# mattduino_mega_nano_v7.net
KiCad netlist of a schematic drawn in EAGLE
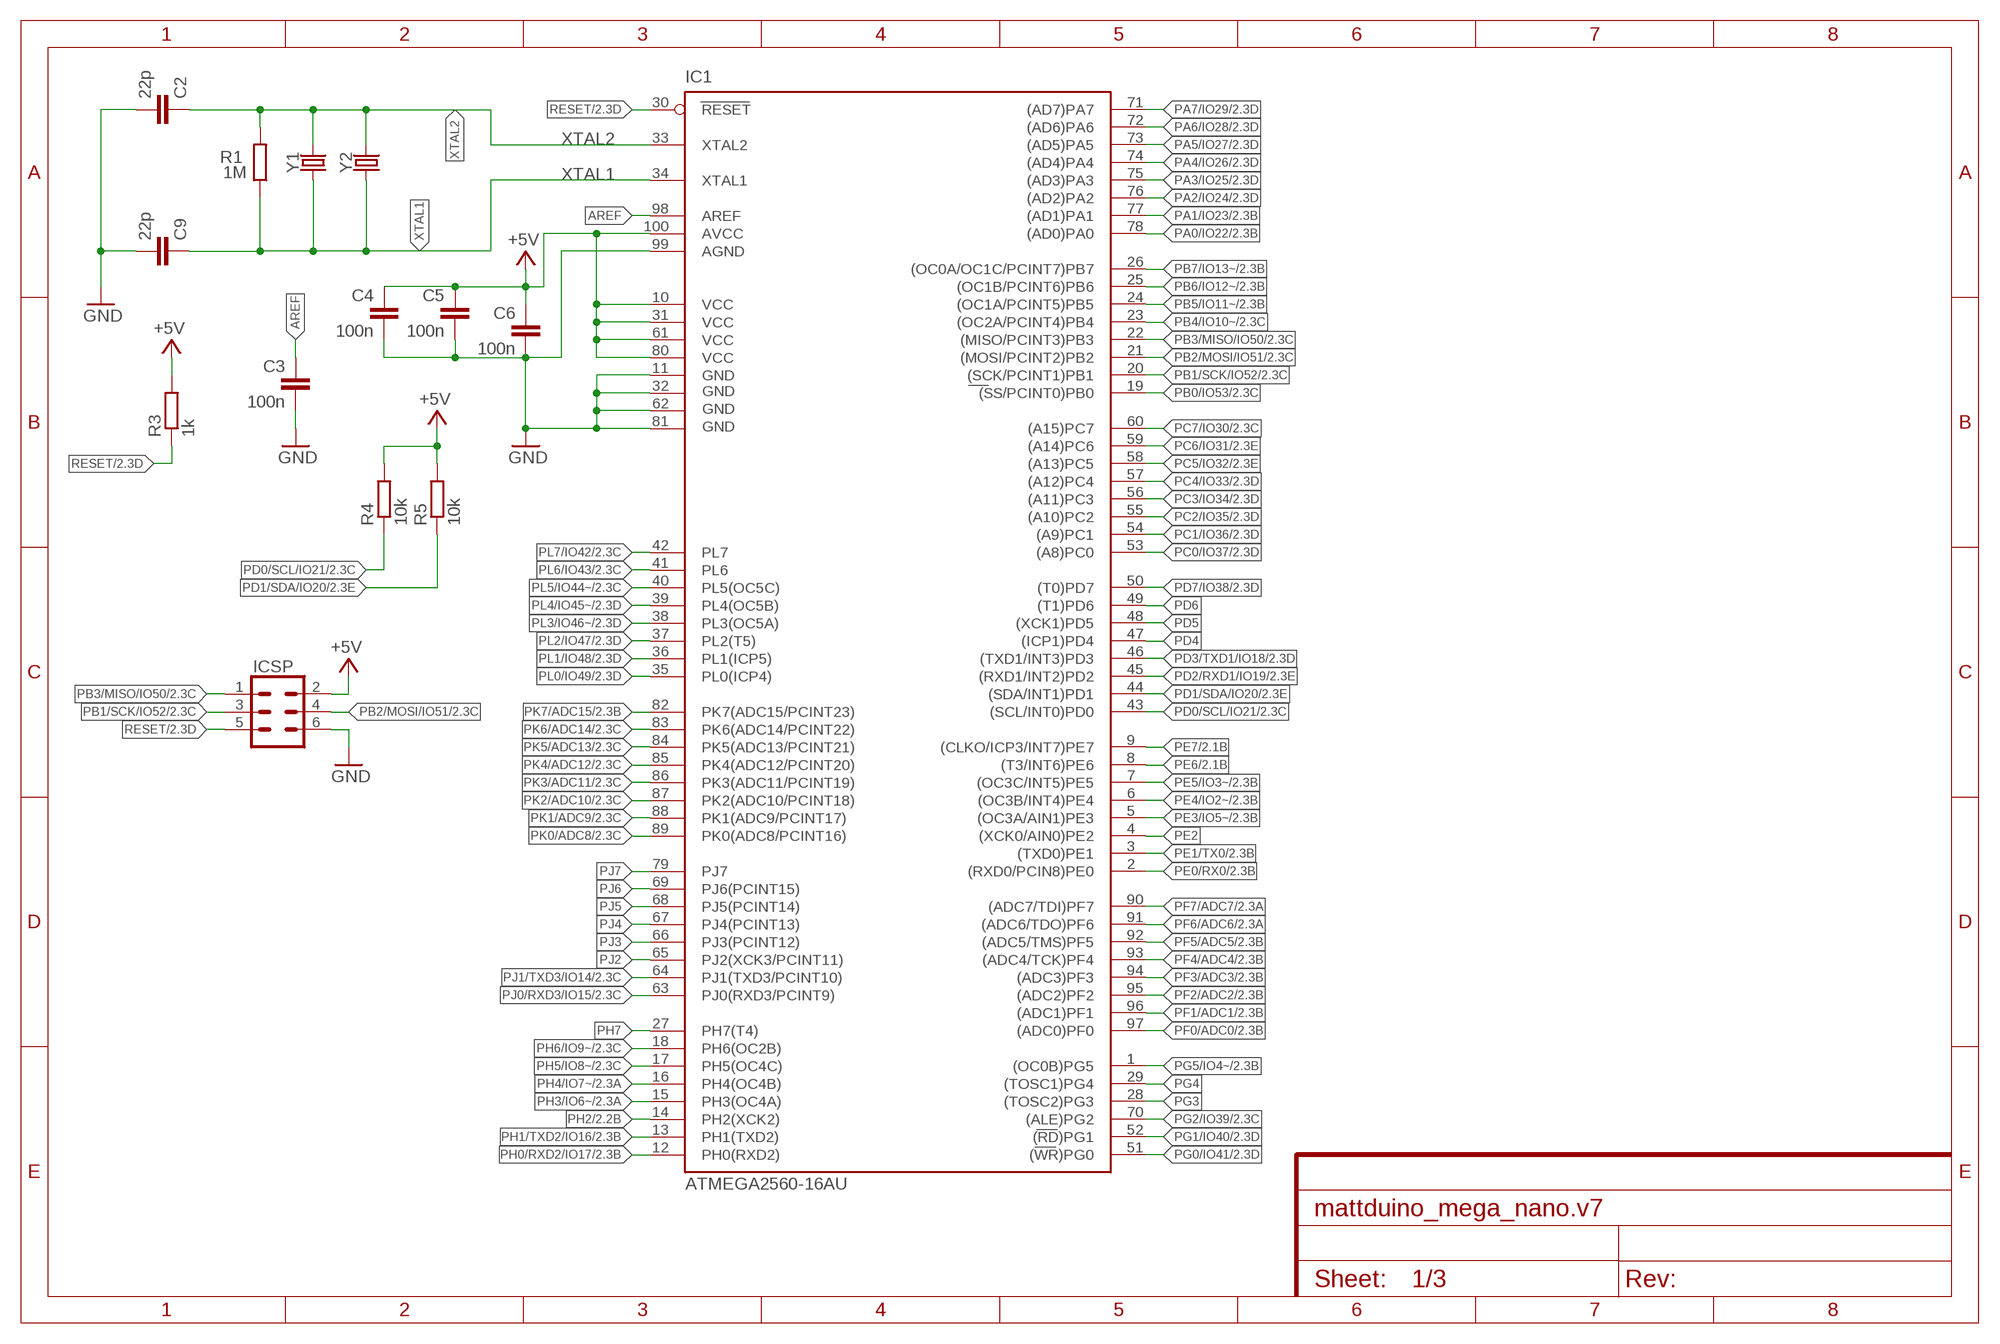
[diagram p0: schematic, sheet 1]
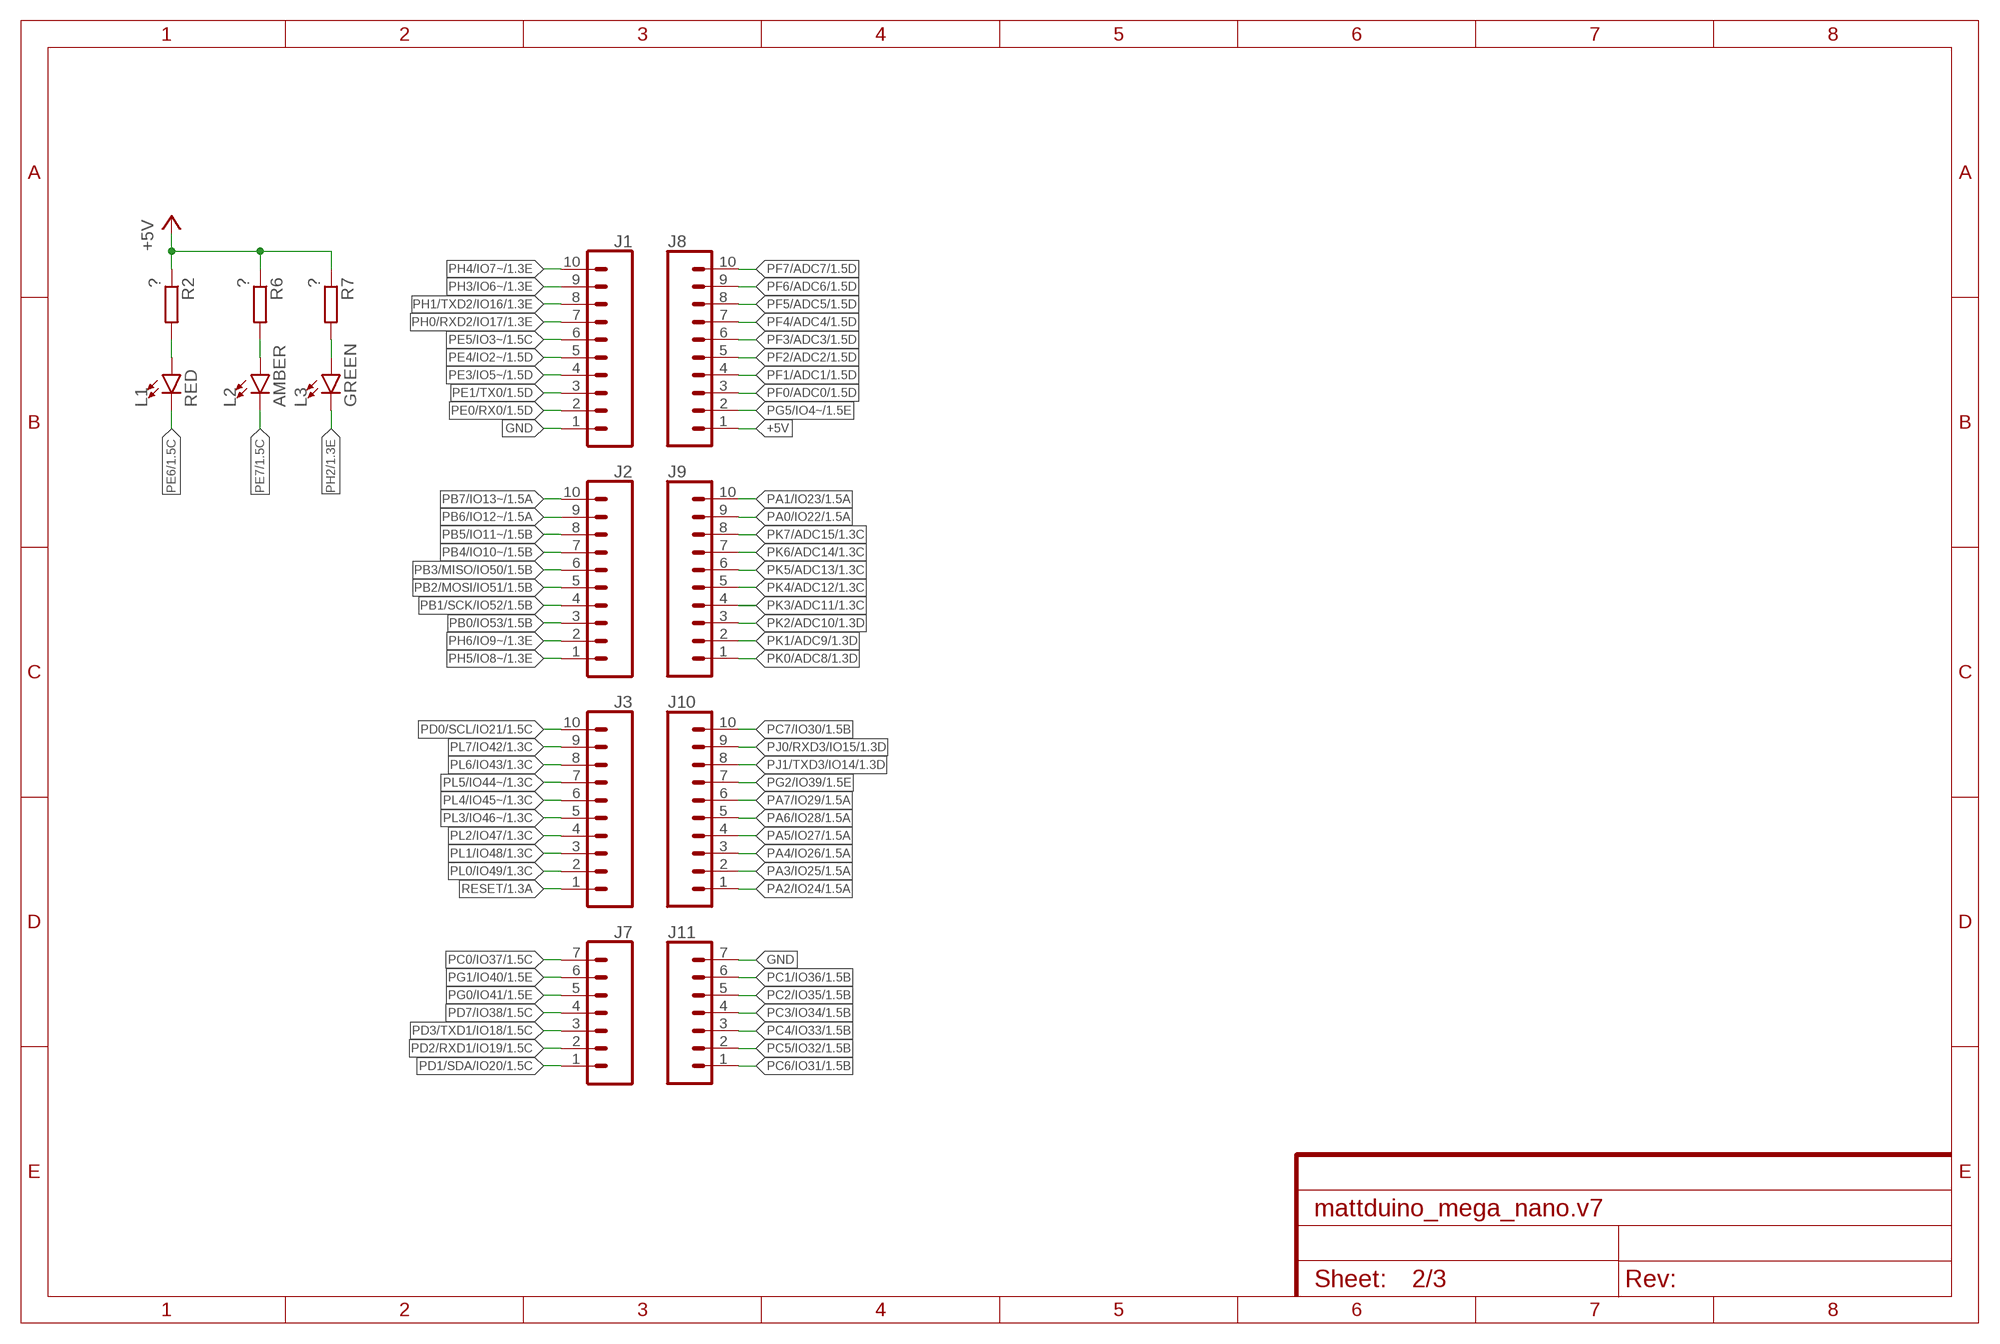
[diagram p1: schematic, sheet 2]
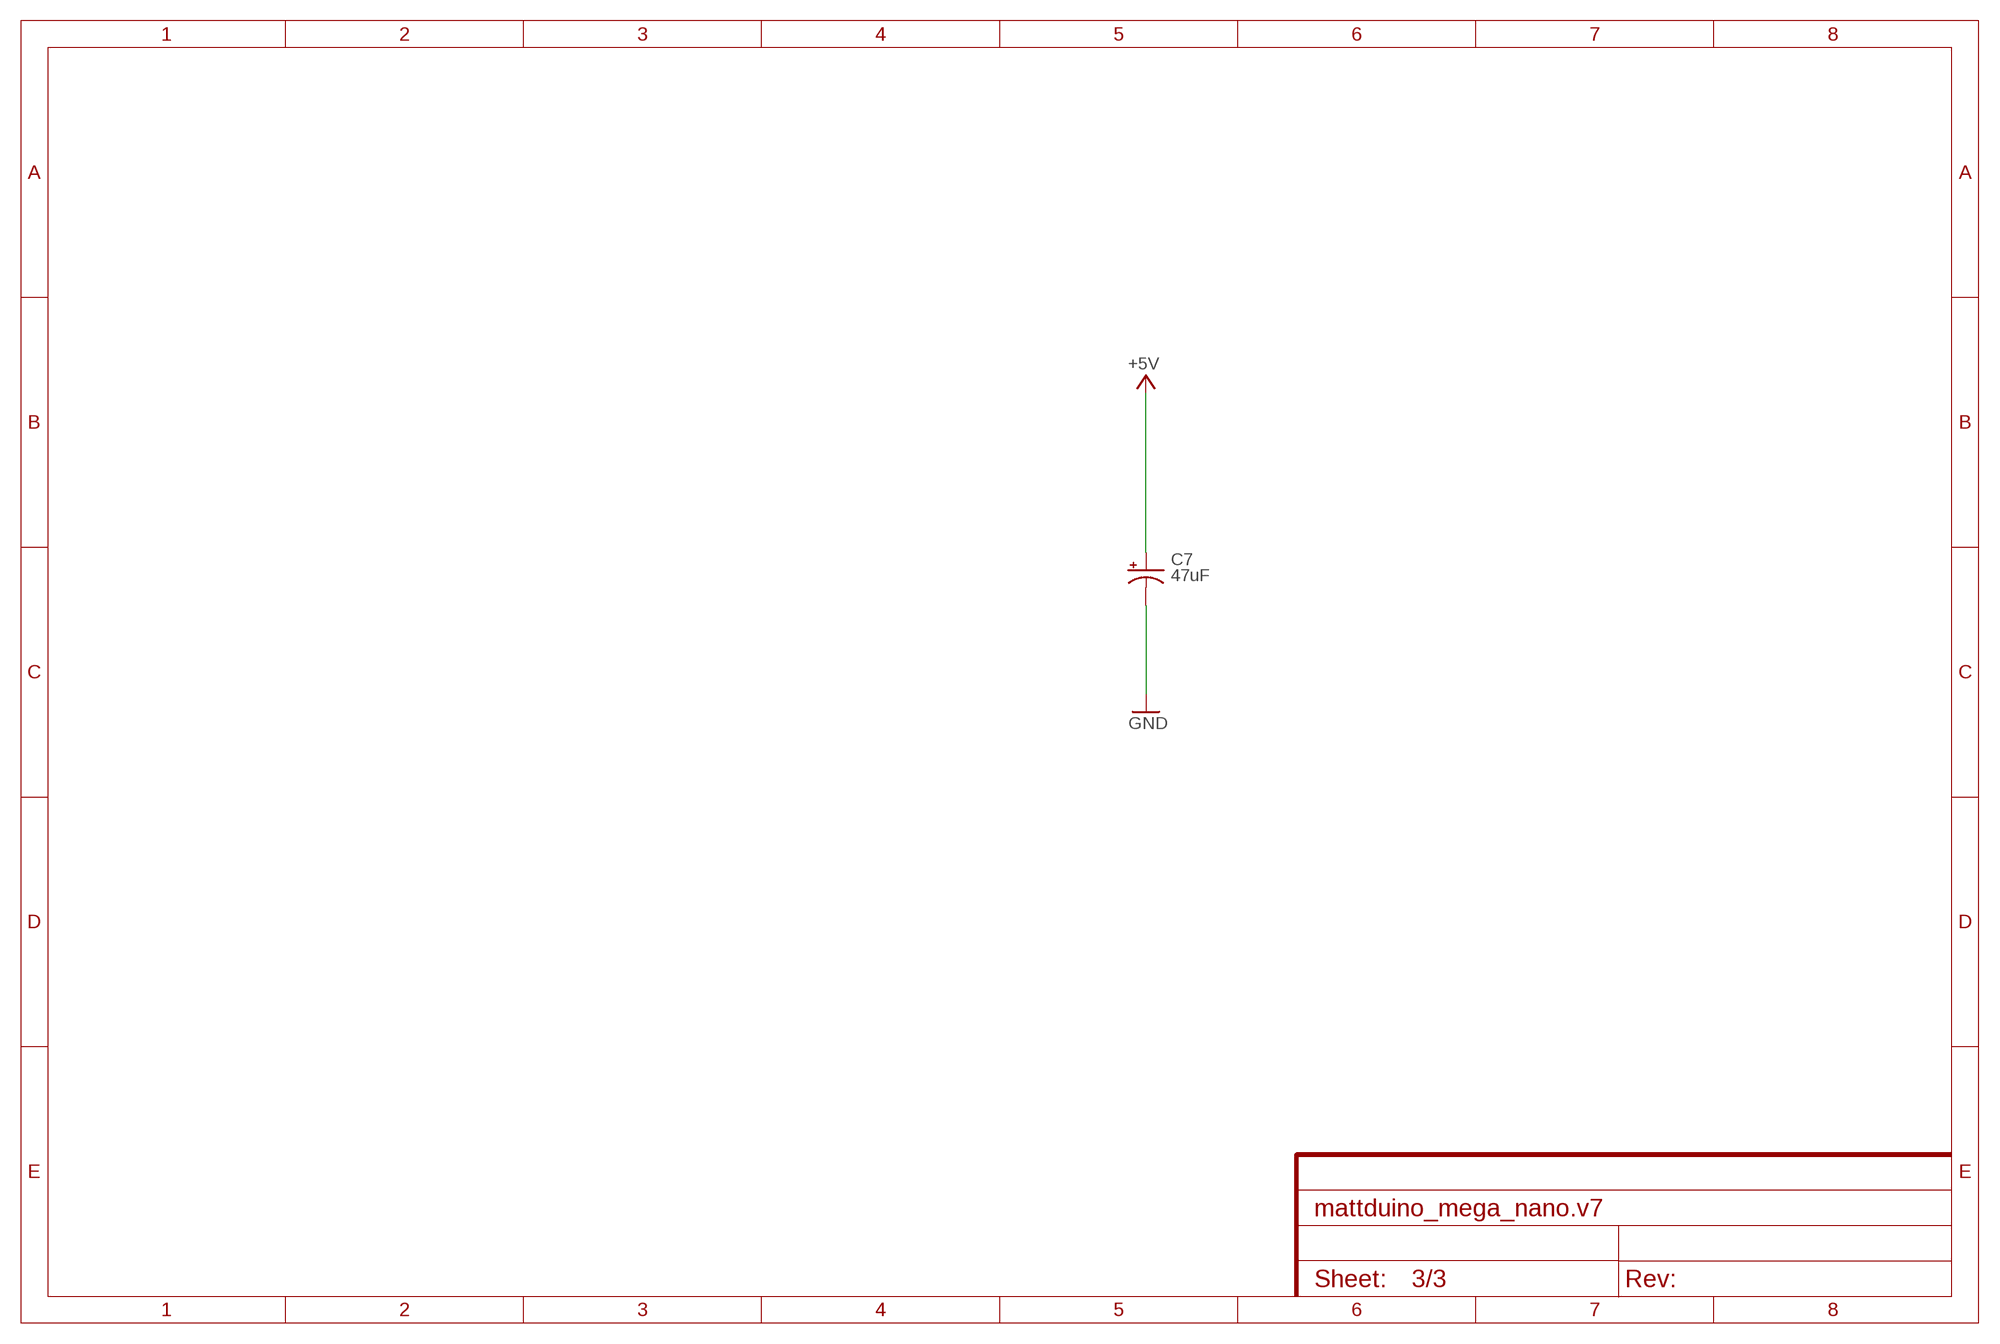
[diagram p2: schematic, sheet 3]

(export (version "E")
  (design (tool "Eeschema 10.0.6"))
  (components
    (comp (ref "J1")
      (value "CONN_10LOCK")
      (footprint "eagle-import:1X10_LOCK")
      (libsource (lib "eagle-import") (part "CONN_10LOCK"))
    )
    (comp (ref "J2")
      (value "CONN_10LOCK")
      (footprint "eagle-import:1X10_LOCK")
      (libsource (lib "eagle-import") (part "CONN_10LOCK"))
    )
    (comp (ref "J3")
      (value "CONN_10LOCK")
      (footprint "eagle-import:1X10_LOCK")
      (libsource (lib "eagle-import") (part "CONN_10LOCK"))
    )
    (comp (ref "J7")
      (value "CONN_07LOCK")
      (footprint "eagle-import:1X07_LOCK")
      (libsource (lib "eagle-import") (part "CONN_07LOCK"))
    )
    (comp (ref "J8")
      (value "CONN_10LOCK")
      (footprint "eagle-import:1X10_LOCK")
      (libsource (lib "eagle-import") (part "CONN_10LOCK"))
    )
    (comp (ref "J9")
      (value "CONN_10LOCK")
      (footprint "eagle-import:1X10_LOCK")
      (libsource (lib "eagle-import") (part "CONN_10LOCK"))
    )
    (comp (ref "J10")
      (value "CONN_10LOCK")
      (footprint "eagle-import:1X10_LOCK")
      (libsource (lib "eagle-import") (part "CONN_10LOCK"))
    )
    (comp (ref "J11")
      (value "CONN_07LOCK")
      (footprint "eagle-import:1X07_LOCK")
      (libsource (lib "eagle-import") (part "CONN_07LOCK"))
    )
    (comp (ref "L1")
      (value "RED")
      (footprint "eagle-import:LED-0603")
      (libsource (lib "eagle-import") (part "LED0603"))
    )
    (comp (ref "L2")
      (value "AMBER")
      (footprint "eagle-import:LED-0603")
      (libsource (lib "eagle-import") (part "LED0603"))
    )
    (comp (ref "L3")
      (value "GREEN")
      (footprint "eagle-import:LED-0603")
      (libsource (lib "eagle-import") (part "LED0603"))
    )
    (comp (ref "R2")
      (value "?")
      (footprint "eagle-import:R0603")
      (libsource (lib "eagle-import") (part "R-EU_R0603"))
    )
    (comp (ref "R6")
      (value "?")
      (footprint "eagle-import:R0603")
      (libsource (lib "eagle-import") (part "R-EU_R0603"))
    )
    (comp (ref "R7")
      (value "?")
      (footprint "eagle-import:R0603")
      (libsource (lib "eagle-import") (part "R-EU_R0603"))
    )
    (comp (ref "C2")
      (value "22p")
      (footprint "eagle-import:C0603")
      (libsource (lib "eagle-import") (part "C-EUC0603"))
    )
    (comp (ref "C3")
      (value "100n")
      (footprint "eagle-import:C0603")
      (libsource (lib "eagle-import") (part "C-EUC0603"))
    )
    (comp (ref "C4")
      (value "100n")
      (footprint "eagle-import:C0603")
      (libsource (lib "eagle-import") (part "C-EUC0603"))
    )
    (comp (ref "C5")
      (value "100n")
      (footprint "eagle-import:C0603")
      (libsource (lib "eagle-import") (part "C-EUC0603"))
    )
    (comp (ref "C6")
      (value "100n")
      (footprint "eagle-import:C0603")
      (libsource (lib "eagle-import") (part "C-EUC0603"))
    )
    (comp (ref "C9")
      (value "22p")
      (footprint "eagle-import:C0603")
      (libsource (lib "eagle-import") (part "C-EUC0603"))
    )
    (comp (ref "IC1")
      (value "ATMEGA2560-16AU")
      (footprint "eagle-import:TQFP100")
      (libsource (lib "eagle-import") (part "ATMEGA2560AU2560-16"))
    )
    (comp (ref "ICSP")
      (value "CONN_03X2SHROUD")
      (footprint "eagle-import:2X3-SHROUDED")
      (libsource (lib "eagle-import") (part "CONN_03X2SHROUD"))
    )
    (comp (ref "R1")
      (value "1M")
      (footprint "eagle-import:R0603")
      (libsource (lib "eagle-import") (part "R-EU_R0603"))
    )
    (comp (ref "R3")
      (value "1k")
      (footprint "eagle-import:R0603")
      (libsource (lib "eagle-import") (part "R-EU_R0603"))
    )
    (comp (ref "R4")
      (value "10k")
      (footprint "eagle-import:R0603")
      (libsource (lib "eagle-import") (part "R-EU_R0603"))
    )
    (comp (ref "R5")
      (value "10k")
      (footprint "eagle-import:R0603")
      (libsource (lib "eagle-import") (part "R-EU_R0603"))
    )
    (comp (ref "Y1")
      (value "CRYSTALPTH-HC49UV")
      (footprint "eagle-import:HC49U")
      (libsource (lib "eagle-import") (part "CRYSTALPTH-HC49UV"))
    )
    (comp (ref "Y2")
      (value "CRYSTALSMD-HC49UP")
      (footprint "eagle-import:HC49UP")
      (libsource (lib "eagle-import") (part "CRYSTALSMD-HC49UP"))
    )
    (comp (ref "C7")
      (value "47uF")
      (footprint "eagle-import:PANASONIC_D")
      (libsource (lib "eagle-import") (part "47UF-POLAR-PANASONIC_D-35V-20%"))
    )
  )
  (nets
    (net (code "1") (name "+5V") (class "Default")
      (node (ref "C4") (pin "1") (pinfunction "1_1") (pintype "passive"))
      (node (ref "C5") (pin "1") (pinfunction "1_1") (pintype "passive"))
      (node (ref "C6") (pin "1") (pinfunction "1_1") (pintype "passive"))
      (node (ref "C7") (pin "+") (pinfunction "+_+") (pintype "passive"))
      (node (ref "IC1") (pin "10") (pinfunction "VCC_10") (pintype "power_in"))
      (node (ref "IC1") (pin "100") (pinfunction "AVCC_100") (pintype "power_in"))
      (node (ref "IC1") (pin "31") (pinfunction "VCC1_31") (pintype "power_in"))
      (node (ref "IC1") (pin "61") (pinfunction "VCC2_61") (pintype "power_in"))
      (node (ref "IC1") (pin "80") (pinfunction "VCC3_80") (pintype "power_in"))
      (node (ref "ICSP") (pin "2") (pinfunction "2_2") (pintype "bidirectional"))
      (node (ref "J8") (pin "1") (pinfunction "1_1") (pintype "passive"))
      (node (ref "R2") (pin "1") (pinfunction "1_1") (pintype "passive"))
      (node (ref "R3") (pin "2") (pinfunction "2_2") (pintype "passive"))
      (node (ref "R4") (pin "2") (pinfunction "2_2") (pintype "passive"))
      (node (ref "R5") (pin "2") (pinfunction "2_2") (pintype "passive"))
      (node (ref "R6") (pin "1") (pinfunction "1_1") (pintype "passive"))
      (node (ref "R7") (pin "1") (pinfunction "1_1") (pintype "passive"))
    )
    (net (code "2") (name "AREF") (class "Default")
      (node (ref "C3") (pin "1") (pinfunction "1_1") (pintype "passive"))
      (node (ref "IC1") (pin "98") (pinfunction "AREF_98") (pintype "bidirectional"))
    )
    (net (code "3") (name "GND") (class "Default")
      (node (ref "C2") (pin "2") (pinfunction "2_2") (pintype "passive"))
      (node (ref "C3") (pin "2") (pinfunction "2_2") (pintype "passive"))
      (node (ref "C4") (pin "2") (pinfunction "2_2") (pintype "passive"))
      (node (ref "C5") (pin "2") (pinfunction "2_2") (pintype "passive"))
      (node (ref "C6") (pin "2") (pinfunction "2_2") (pintype "passive"))
      (node (ref "C7") (pin "-") (pinfunction "-_-") (pintype "passive"))
      (node (ref "C9") (pin "2") (pinfunction "2_2") (pintype "passive"))
      (node (ref "IC1") (pin "11") (pinfunction "GND_11") (pintype "power_in"))
      (node (ref "IC1") (pin "32") (pinfunction "GND1_32") (pintype "power_in"))
      (node (ref "IC1") (pin "62") (pinfunction "GND2_62") (pintype "power_in"))
      (node (ref "IC1") (pin "81") (pinfunction "GND3_81") (pintype "power_in"))
      (node (ref "IC1") (pin "99") (pinfunction "AGND_99") (pintype "power_in"))
      (node (ref "ICSP") (pin "6") (pinfunction "6_6") (pintype "bidirectional"))
      (node (ref "J1") (pin "1") (pinfunction "1_1") (pintype "passive"))
      (node (ref "J11") (pin "7") (pinfunction "7_7") (pintype "passive"))
    )
    (net (code "4") (name "Net-(L1-PadA)") (class "Default")
      (node (ref "L1") (pin "A") (pinfunction "A_A") (pintype "passive"))
      (node (ref "R2") (pin "2") (pinfunction "2_2") (pintype "passive"))
    )
    (net (code "5") (name "Net-(L2-PadA)") (class "Default")
      (node (ref "L2") (pin "A") (pinfunction "A_A") (pintype "passive"))
      (node (ref "R6") (pin "2") (pinfunction "2_2") (pintype "passive"))
    )
    (net (code "6") (name "Net-(L3-PadA)") (class "Default")
      (node (ref "L3") (pin "A") (pinfunction "A_A") (pintype "passive"))
      (node (ref "R7") (pin "2") (pinfunction "2_2") (pintype "passive"))
    )
    (net (code "7") (name "PA0{slash}IO22") (class "Default")
      (node (ref "IC1") (pin "78") (pinfunction "(AD0)PA0_78") (pintype "bidirectional"))
      (node (ref "J9") (pin "9") (pinfunction "9_9") (pintype "passive"))
    )
    (net (code "8") (name "PA1{slash}IO23") (class "Default")
      (node (ref "IC1") (pin "77") (pinfunction "(AD1)PA1_77") (pintype "bidirectional"))
      (node (ref "J9") (pin "10") (pinfunction "10_10") (pintype "passive"))
    )
    (net (code "9") (name "PA2{slash}IO24") (class "Default")
      (node (ref "IC1") (pin "76") (pinfunction "(AD2)PA2_76") (pintype "bidirectional"))
      (node (ref "J10") (pin "1") (pinfunction "1_1") (pintype "passive"))
    )
    (net (code "10") (name "PA3{slash}IO25") (class "Default")
      (node (ref "IC1") (pin "75") (pinfunction "(AD3)PA3_75") (pintype "bidirectional"))
      (node (ref "J10") (pin "2") (pinfunction "2_2") (pintype "passive"))
    )
    (net (code "11") (name "PA4{slash}IO26") (class "Default")
      (node (ref "IC1") (pin "74") (pinfunction "(AD4)PA4_74") (pintype "bidirectional"))
      (node (ref "J10") (pin "3") (pinfunction "3_3") (pintype "passive"))
    )
    (net (code "12") (name "PA5{slash}IO27") (class "Default")
      (node (ref "IC1") (pin "73") (pinfunction "(AD5)PA5_73") (pintype "bidirectional"))
      (node (ref "J10") (pin "4") (pinfunction "4_4") (pintype "passive"))
    )
    (net (code "13") (name "PA6{slash}IO28") (class "Default")
      (node (ref "IC1") (pin "72") (pinfunction "(AD6)PA6_72") (pintype "bidirectional"))
      (node (ref "J10") (pin "5") (pinfunction "5_5") (pintype "passive"))
    )
    (net (code "14") (name "PA7{slash}IO29") (class "Default")
      (node (ref "IC1") (pin "71") (pinfunction "(AD7)PA7_71") (pintype "bidirectional"))
      (node (ref "J10") (pin "6") (pinfunction "6_6") (pintype "passive"))
    )
    (net (code "15") (name "PB0{slash}IO53") (class "Default")
      (node (ref "IC1") (pin "19") (pinfunction "(SS/PCINT0)PB0_19") (pintype "bidirectional"))
      (node (ref "J2") (pin "3") (pinfunction "3_3") (pintype "passive"))
    )
    (net (code "16") (name "PB1{slash}SCK{slash}IO52") (class "Default")
      (node (ref "IC1") (pin "20") (pinfunction "(SCK/PCINT1)PB1_20") (pintype "bidirectional"))
      (node (ref "ICSP") (pin "3") (pinfunction "3_3") (pintype "bidirectional"))
      (node (ref "J2") (pin "4") (pinfunction "4_4") (pintype "passive"))
    )
    (net (code "17") (name "PB2{slash}MOSI{slash}IO51") (class "Default")
      (node (ref "IC1") (pin "21") (pinfunction "(MOSI/PCINT2)PB2_21") (pintype "bidirectional"))
      (node (ref "ICSP") (pin "4") (pinfunction "4_4") (pintype "bidirectional"))
      (node (ref "J2") (pin "5") (pinfunction "5_5") (pintype "passive"))
    )
    (net (code "18") (name "PB3{slash}MISO{slash}IO50") (class "Default")
      (node (ref "IC1") (pin "22") (pinfunction "(MISO/PCINT3)PB3_22") (pintype "bidirectional"))
      (node (ref "ICSP") (pin "1") (pinfunction "1_1") (pintype "bidirectional"))
      (node (ref "J2") (pin "6") (pinfunction "6_6") (pintype "passive"))
    )
    (net (code "19") (name "PB4{slash}IO10~{}") (class "Default")
      (node (ref "IC1") (pin "23") (pinfunction "(OC2A/PCINT4)PB4_23") (pintype "bidirectional"))
      (node (ref "J2") (pin "7") (pinfunction "7_7") (pintype "passive"))
    )
    (net (code "20") (name "PB5{slash}IO11~{}") (class "Default")
      (node (ref "IC1") (pin "24") (pinfunction "(OC1A/PCINT5)PB5_24") (pintype "bidirectional"))
      (node (ref "J2") (pin "8") (pinfunction "8_8") (pintype "passive"))
    )
    (net (code "21") (name "PB6{slash}IO12~{}") (class "Default")
      (node (ref "IC1") (pin "25") (pinfunction "(OC1B/PCINT6)PB6_25") (pintype "bidirectional"))
      (node (ref "J2") (pin "9") (pinfunction "9_9") (pintype "passive"))
    )
    (net (code "22") (name "PB7{slash}IO13~{}") (class "Default")
      (node (ref "IC1") (pin "26") (pinfunction "(OC0A/OC1C/PCINT7)PB7_26") (pintype "bidirectional"))
      (node (ref "J2") (pin "10") (pinfunction "10_10") (pintype "passive"))
    )
    (net (code "23") (name "PC0{slash}IO37") (class "Default")
      (node (ref "IC1") (pin "53") (pinfunction "(A8)PC0_53") (pintype "bidirectional"))
      (node (ref "J7") (pin "7") (pinfunction "7_7") (pintype "passive"))
    )
    (net (code "24") (name "PC1{slash}IO36") (class "Default")
      (node (ref "IC1") (pin "54") (pinfunction "(A9)PC1_54") (pintype "bidirectional"))
      (node (ref "J11") (pin "6") (pinfunction "6_6") (pintype "passive"))
    )
    (net (code "25") (name "PC2{slash}IO35") (class "Default")
      (node (ref "IC1") (pin "55") (pinfunction "(A10)PC2_55") (pintype "bidirectional"))
      (node (ref "J11") (pin "5") (pinfunction "5_5") (pintype "passive"))
    )
    (net (code "26") (name "PC3{slash}IO34") (class "Default")
      (node (ref "IC1") (pin "56") (pinfunction "(A11)PC3_56") (pintype "bidirectional"))
      (node (ref "J11") (pin "4") (pinfunction "4_4") (pintype "passive"))
    )
    (net (code "27") (name "PC4{slash}IO33") (class "Default")
      (node (ref "IC1") (pin "57") (pinfunction "(A12)PC4_57") (pintype "bidirectional"))
      (node (ref "J11") (pin "3") (pinfunction "3_3") (pintype "passive"))
    )
    (net (code "28") (name "PC5{slash}IO32") (class "Default")
      (node (ref "IC1") (pin "58") (pinfunction "(A13)PC5_58") (pintype "bidirectional"))
      (node (ref "J11") (pin "2") (pinfunction "2_2") (pintype "passive"))
    )
    (net (code "29") (name "PC6{slash}IO31") (class "Default")
      (node (ref "IC1") (pin "59") (pinfunction "(A14)PC6_59") (pintype "bidirectional"))
      (node (ref "J11") (pin "1") (pinfunction "1_1") (pintype "passive"))
    )
    (net (code "30") (name "PC7{slash}IO30") (class "Default")
      (node (ref "IC1") (pin "60") (pinfunction "(A15)PC7_60") (pintype "bidirectional"))
      (node (ref "J10") (pin "10") (pinfunction "10_10") (pintype "passive"))
    )
    (net (code "31") (name "PD0{slash}SCL{slash}IO21") (class "Default")
      (node (ref "IC1") (pin "43") (pinfunction "(SCL/INT0)PD0_43") (pintype "bidirectional"))
      (node (ref "J3") (pin "10") (pinfunction "10_10") (pintype "passive"))
      (node (ref "R4") (pin "1") (pinfunction "1_1") (pintype "passive"))
    )
    (net (code "32") (name "PD1{slash}SDA{slash}IO20") (class "Default")
      (node (ref "IC1") (pin "44") (pinfunction "(SDA/INT1)PD1_44") (pintype "bidirectional"))
      (node (ref "J7") (pin "1") (pinfunction "1_1") (pintype "passive"))
      (node (ref "R5") (pin "1") (pinfunction "1_1") (pintype "passive"))
    )
    (net (code "33") (name "PD2{slash}RXD1{slash}IO19") (class "Default")
      (node (ref "IC1") (pin "45") (pinfunction "(RXD1/INT2)PD2_45") (pintype "bidirectional"))
      (node (ref "J7") (pin "2") (pinfunction "2_2") (pintype "passive"))
    )
    (net (code "34") (name "PD3{slash}TXD1{slash}IO18") (class "Default")
      (node (ref "IC1") (pin "46") (pinfunction "(TXD1/INT3)PD3_46") (pintype "bidirectional"))
      (node (ref "J7") (pin "3") (pinfunction "3_3") (pintype "passive"))
    )
    (net (code "35") (name "PD4") (class "Default")
      (node (ref "IC1") (pin "47") (pinfunction "(ICP1)PD4_47") (pintype "bidirectional"))
    )
    (net (code "36") (name "PD5") (class "Default")
      (node (ref "IC1") (pin "48") (pinfunction "(XCK1)PD5_48") (pintype "bidirectional"))
    )
    (net (code "37") (name "PD6") (class "Default")
      (node (ref "IC1") (pin "49") (pinfunction "(T1)PD6_49") (pintype "bidirectional"))
    )
    (net (code "38") (name "PD7{slash}IO38") (class "Default")
      (node (ref "IC1") (pin "50") (pinfunction "(T0)PD7_50") (pintype "bidirectional"))
      (node (ref "J7") (pin "4") (pinfunction "4_4") (pintype "passive"))
    )
    (net (code "39") (name "PE0{slash}RX0") (class "Default")
      (node (ref "IC1") (pin "2") (pinfunction "(RXD0/PCIN8)PE0_2") (pintype "bidirectional"))
      (node (ref "J1") (pin "2") (pinfunction "2_2") (pintype "passive"))
    )
    (net (code "40") (name "PE1{slash}TX0") (class "Default")
      (node (ref "IC1") (pin "3") (pinfunction "(TXD0)PE1_3") (pintype "bidirectional"))
      (node (ref "J1") (pin "3") (pinfunction "3_3") (pintype "passive"))
    )
    (net (code "41") (name "PE2") (class "Default")
      (node (ref "IC1") (pin "4") (pinfunction "(XCK0/AIN0)PE2_4") (pintype "bidirectional"))
    )
    (net (code "42") (name "PE3{slash}IO5~{}") (class "Default")
      (node (ref "IC1") (pin "5") (pinfunction "(OC3A/AIN1)PE3_5") (pintype "bidirectional"))
      (node (ref "J1") (pin "4") (pinfunction "4_4") (pintype "passive"))
    )
    (net (code "43") (name "PE4{slash}IO2~{}") (class "Default")
      (node (ref "IC1") (pin "6") (pinfunction "(OC3B/INT4)PE4_6") (pintype "bidirectional"))
      (node (ref "J1") (pin "5") (pinfunction "5_5") (pintype "passive"))
    )
    (net (code "44") (name "PE5{slash}IO3~{}") (class "Default")
      (node (ref "IC1") (pin "7") (pinfunction "(OC3C/INT5)PE5_7") (pintype "bidirectional"))
      (node (ref "J1") (pin "6") (pinfunction "6_6") (pintype "passive"))
    )
    (net (code "45") (name "PE6") (class "Default")
      (node (ref "IC1") (pin "8") (pinfunction "(T3/INT6)PE6_8") (pintype "bidirectional"))
      (node (ref "L1") (pin "C") (pinfunction "C_C") (pintype "passive"))
    )
    (net (code "46") (name "PE7") (class "Default")
      (node (ref "IC1") (pin "9") (pinfunction "(CLKO/ICP3/INT7)PE7_9") (pintype "bidirectional"))
      (node (ref "L2") (pin "C") (pinfunction "C_C") (pintype "passive"))
    )
    (net (code "47") (name "PF0{slash}ADC0") (class "Default")
      (node (ref "IC1") (pin "97") (pinfunction "(ADC0)PF0_97") (pintype "bidirectional"))
      (node (ref "J8") (pin "3") (pinfunction "3_3") (pintype "passive"))
    )
    (net (code "48") (name "PF1{slash}ADC1") (class "Default")
      (node (ref "IC1") (pin "96") (pinfunction "(ADC1)PF1_96") (pintype "bidirectional"))
      (node (ref "J8") (pin "4") (pinfunction "4_4") (pintype "passive"))
    )
    (net (code "49") (name "PF2{slash}ADC2") (class "Default")
      (node (ref "IC1") (pin "95") (pinfunction "(ADC2)PF2_95") (pintype "bidirectional"))
      (node (ref "J8") (pin "5") (pinfunction "5_5") (pintype "passive"))
    )
    (net (code "50") (name "PF3{slash}ADC3") (class "Default")
      (node (ref "IC1") (pin "94") (pinfunction "(ADC3)PF3_94") (pintype "bidirectional"))
      (node (ref "J8") (pin "6") (pinfunction "6_6") (pintype "passive"))
    )
    (net (code "51") (name "PF4{slash}ADC4") (class "Default")
      (node (ref "IC1") (pin "93") (pinfunction "(ADC4/TCK)PF4_93") (pintype "bidirectional"))
      (node (ref "J8") (pin "7") (pinfunction "7_7") (pintype "passive"))
    )
    (net (code "52") (name "PF5{slash}ADC5") (class "Default")
      (node (ref "IC1") (pin "92") (pinfunction "(ADC5/TMS)PF5_92") (pintype "bidirectional"))
      (node (ref "J8") (pin "8") (pinfunction "8_8") (pintype "passive"))
    )
    (net (code "53") (name "PF6{slash}ADC6") (class "Default")
      (node (ref "IC1") (pin "91") (pinfunction "(ADC6/TDO)PF6_91") (pintype "bidirectional"))
      (node (ref "J8") (pin "9") (pinfunction "9_9") (pintype "passive"))
    )
    (net (code "54") (name "PF7{slash}ADC7") (class "Default")
      (node (ref "IC1") (pin "90") (pinfunction "(ADC7/TDI)PF7_90") (pintype "bidirectional"))
      (node (ref "J8") (pin "10") (pinfunction "10_10") (pintype "passive"))
    )
    (net (code "55") (name "PG0{slash}IO41") (class "Default")
      (node (ref "IC1") (pin "51") (pinfunction "(WR)PG0_51") (pintype "bidirectional"))
      (node (ref "J7") (pin "5") (pinfunction "5_5") (pintype "passive"))
    )
    (net (code "56") (name "PG1{slash}IO40") (class "Default")
      (node (ref "IC1") (pin "52") (pinfunction "(RD)PG1_52") (pintype "bidirectional"))
      (node (ref "J7") (pin "6") (pinfunction "6_6") (pintype "passive"))
    )
    (net (code "57") (name "PG2{slash}IO39") (class "Default")
      (node (ref "IC1") (pin "70") (pinfunction "(ALE)PG2_70") (pintype "bidirectional"))
      (node (ref "J10") (pin "7") (pinfunction "7_7") (pintype "passive"))
    )
    (net (code "58") (name "PG3") (class "Default")
      (node (ref "IC1") (pin "28") (pinfunction "(TOSC2)PG3_28") (pintype "bidirectional"))
    )
    (net (code "59") (name "PG4") (class "Default")
      (node (ref "IC1") (pin "29") (pinfunction "(TOSC1)PG4_29") (pintype "bidirectional"))
    )
    (net (code "60") (name "PG5{slash}IO4~{}") (class "Default")
      (node (ref "IC1") (pin "1") (pinfunction "(OC0B)PG5_1") (pintype "bidirectional"))
      (node (ref "J8") (pin "2") (pinfunction "2_2") (pintype "passive"))
    )
    (net (code "61") (name "PH0{slash}RXD2{slash}IO17") (class "Default")
      (node (ref "IC1") (pin "12") (pinfunction "PH0(RXD2)_12") (pintype "bidirectional"))
      (node (ref "J1") (pin "7") (pinfunction "7_7") (pintype "passive"))
    )
    (net (code "62") (name "PH1{slash}TXD2{slash}IO16") (class "Default")
      (node (ref "IC1") (pin "13") (pinfunction "PH1(TXD2)_13") (pintype "bidirectional"))
      (node (ref "J1") (pin "8") (pinfunction "8_8") (pintype "passive"))
    )
    (net (code "63") (name "PH2") (class "Default")
      (node (ref "IC1") (pin "14") (pinfunction "PH2(XCK2)_14") (pintype "bidirectional"))
      (node (ref "L3") (pin "C") (pinfunction "C_C") (pintype "passive"))
    )
    (net (code "64") (name "PH3{slash}IO6~{}") (class "Default")
      (node (ref "IC1") (pin "15") (pinfunction "PH3(OC4A)_15") (pintype "bidirectional"))
      (node (ref "J1") (pin "9") (pinfunction "9_9") (pintype "passive"))
    )
    (net (code "65") (name "PH4{slash}IO7~{}") (class "Default")
      (node (ref "IC1") (pin "16") (pinfunction "PH4(OC4B)_16") (pintype "bidirectional"))
      (node (ref "J1") (pin "10") (pinfunction "10_10") (pintype "passive"))
    )
    (net (code "66") (name "PH5{slash}IO8~{}") (class "Default")
      (node (ref "IC1") (pin "17") (pinfunction "PH5(OC4C)_17") (pintype "bidirectional"))
      (node (ref "J2") (pin "1") (pinfunction "1_1") (pintype "passive"))
    )
    (net (code "67") (name "PH6{slash}IO9~{}") (class "Default")
      (node (ref "IC1") (pin "18") (pinfunction "PH6(OC2B)_18") (pintype "bidirectional"))
      (node (ref "J2") (pin "2") (pinfunction "2_2") (pintype "passive"))
    )
    (net (code "68") (name "PH7") (class "Default")
      (node (ref "IC1") (pin "27") (pinfunction "PH7(T4)_27") (pintype "bidirectional"))
    )
    (net (code "69") (name "PJ0{slash}RXD3{slash}IO15") (class "Default")
      (node (ref "IC1") (pin "63") (pinfunction "PJ0(RXD3/PCINT9)_63") (pintype "bidirectional"))
      (node (ref "J10") (pin "9") (pinfunction "9_9") (pintype "passive"))
    )
    (net (code "70") (name "PJ1{slash}TXD3{slash}IO14") (class "Default")
      (node (ref "IC1") (pin "64") (pinfunction "PJ1(TXD3/PCINT10)_64") (pintype "bidirectional"))
      (node (ref "J10") (pin "8") (pinfunction "8_8") (pintype "passive"))
    )
    (net (code "71") (name "PJ2") (class "Default")
      (node (ref "IC1") (pin "65") (pinfunction "PJ2(XCK3/PCINT11)_65") (pintype "bidirectional"))
    )
    (net (code "72") (name "PJ3") (class "Default")
      (node (ref "IC1") (pin "66") (pinfunction "PJ3(PCINT12)_66") (pintype "bidirectional"))
    )
    (net (code "73") (name "PJ4") (class "Default")
      (node (ref "IC1") (pin "67") (pinfunction "PJ4(PCINT13)_67") (pintype "bidirectional"))
    )
    (net (code "74") (name "PJ5") (class "Default")
      (node (ref "IC1") (pin "68") (pinfunction "PJ5(PCINT14)_68") (pintype "bidirectional"))
    )
    (net (code "75") (name "PJ6") (class "Default")
      (node (ref "IC1") (pin "69") (pinfunction "PJ6(PCINT15)_69") (pintype "bidirectional"))
    )
    (net (code "76") (name "PJ7") (class "Default")
      (node (ref "IC1") (pin "79") (pinfunction "PJ7_79") (pintype "bidirectional"))
    )
    (net (code "77") (name "PK0{slash}ADC8") (class "Default")
      (node (ref "IC1") (pin "89") (pinfunction "PK0(ADC8/PCINT16)_89") (pintype "bidirectional"))
      (node (ref "J9") (pin "1") (pinfunction "1_1") (pintype "passive"))
    )
    (net (code "78") (name "PK1{slash}ADC9") (class "Default")
      (node (ref "IC1") (pin "88") (pinfunction "PK1(ADC9/PCINT17)_88") (pintype "bidirectional"))
      (node (ref "J9") (pin "2") (pinfunction "2_2") (pintype "passive"))
    )
    (net (code "79") (name "PK2{slash}ADC10") (class "Default")
      (node (ref "IC1") (pin "87") (pinfunction "PK2(ADC10/PCINT18)_87") (pintype "bidirectional"))
      (node (ref "J9") (pin "3") (pinfunction "3_3") (pintype "passive"))
    )
    (net (code "80") (name "PK3{slash}ADC11") (class "Default")
      (node (ref "IC1") (pin "86") (pinfunction "PK3(ADC11/PCINT19)_86") (pintype "bidirectional"))
      (node (ref "J9") (pin "4") (pinfunction "4_4") (pintype "passive"))
    )
    (net (code "81") (name "PK4{slash}ADC12") (class "Default")
      (node (ref "IC1") (pin "85") (pinfunction "PK4(ADC12/PCINT20)_85") (pintype "bidirectional"))
      (node (ref "J9") (pin "5") (pinfunction "5_5") (pintype "passive"))
    )
    (net (code "82") (name "PK5{slash}ADC13") (class "Default")
      (node (ref "IC1") (pin "84") (pinfunction "PK5(ADC13/PCINT21)_84") (pintype "bidirectional"))
      (node (ref "J9") (pin "6") (pinfunction "6_6") (pintype "passive"))
    )
    (net (code "83") (name "PK6{slash}ADC14") (class "Default")
      (node (ref "IC1") (pin "83") (pinfunction "PK6(ADC14/PCINT22)_83") (pintype "bidirectional"))
      (node (ref "J9") (pin "7") (pinfunction "7_7") (pintype "passive"))
    )
    (net (code "84") (name "PK7{slash}ADC15") (class "Default")
      (node (ref "IC1") (pin "82") (pinfunction "PK7(ADC15/PCINT23)_82") (pintype "bidirectional"))
      (node (ref "J9") (pin "8") (pinfunction "8_8") (pintype "passive"))
    )
    (net (code "85") (name "PL0{slash}IO49") (class "Default")
      (node (ref "IC1") (pin "35") (pinfunction "PL0(ICP4)_35") (pintype "bidirectional"))
      (node (ref "J3") (pin "2") (pinfunction "2_2") (pintype "passive"))
    )
    (net (code "86") (name "PL1{slash}IO48") (class "Default")
      (node (ref "IC1") (pin "36") (pinfunction "PL1(ICP5)_36") (pintype "bidirectional"))
      (node (ref "J3") (pin "3") (pinfunction "3_3") (pintype "passive"))
    )
    (net (code "87") (name "PL2{slash}IO47") (class "Default")
      (node (ref "IC1") (pin "37") (pinfunction "PL2(T5)_37") (pintype "bidirectional"))
      (node (ref "J3") (pin "4") (pinfunction "4_4") (pintype "passive"))
    )
    (net (code "88") (name "PL3{slash}IO46~{}") (class "Default")
      (node (ref "IC1") (pin "38") (pinfunction "PL3(OC5A)_38") (pintype "bidirectional"))
      (node (ref "J3") (pin "5") (pinfunction "5_5") (pintype "passive"))
    )
    (net (code "89") (name "PL4{slash}IO45~{}") (class "Default")
      (node (ref "IC1") (pin "39") (pinfunction "PL4(OC5B)_39") (pintype "bidirectional"))
      (node (ref "J3") (pin "6") (pinfunction "6_6") (pintype "passive"))
    )
    (net (code "90") (name "PL5{slash}IO44~{}") (class "Default")
      (node (ref "IC1") (pin "40") (pinfunction "PL5(OC5C)_40") (pintype "bidirectional"))
      (node (ref "J3") (pin "7") (pinfunction "7_7") (pintype "passive"))
    )
    (net (code "91") (name "PL6{slash}IO43") (class "Default")
      (node (ref "IC1") (pin "41") (pinfunction "PL6_41") (pintype "bidirectional"))
      (node (ref "J3") (pin "8") (pinfunction "8_8") (pintype "passive"))
    )
    (net (code "92") (name "PL7{slash}IO42") (class "Default")
      (node (ref "IC1") (pin "42") (pinfunction "PL7_42") (pintype "bidirectional"))
      (node (ref "J3") (pin "9") (pinfunction "9_9") (pintype "passive"))
    )
    (net (code "93") (name "RESET") (class "Default")
      (node (ref "IC1") (pin "30") (pinfunction "RESET_30") (pintype "input"))
      (node (ref "ICSP") (pin "5") (pinfunction "5_5") (pintype "bidirectional"))
      (node (ref "J3") (pin "1") (pinfunction "1_1") (pintype "passive"))
      (node (ref "R3") (pin "1") (pinfunction "1_1") (pintype "passive"))
    )
    (net (code "94") (name "XTAL1") (class "Default")
      (node (ref "C9") (pin "1") (pinfunction "1_1") (pintype "passive"))
      (node (ref "IC1") (pin "34") (pinfunction "XTAL1_34") (pintype "input"))
      (node (ref "R1") (pin "1") (pinfunction "1_1") (pintype "passive"))
      (node (ref "Y1") (pin "1") (pinfunction "1_1") (pintype "passive"))
      (node (ref "Y2") (pin "1") (pinfunction "1_1") (pintype "passive"))
    )
    (net (code "95") (name "XTAL2") (class "Default")
      (node (ref "C2") (pin "1") (pinfunction "1_1") (pintype "passive"))
      (node (ref "IC1") (pin "33") (pinfunction "XTAL2_33") (pintype "output"))
      (node (ref "R1") (pin "2") (pinfunction "2_2") (pintype "passive"))
      (node (ref "Y1") (pin "2") (pinfunction "2_2") (pintype "passive"))
      (node (ref "Y2") (pin "2") (pinfunction "2_2") (pintype "passive"))
    )
  )
)
